# Power_Sensing.net
KiCad netlist of a schematic drawn in Altium Designer
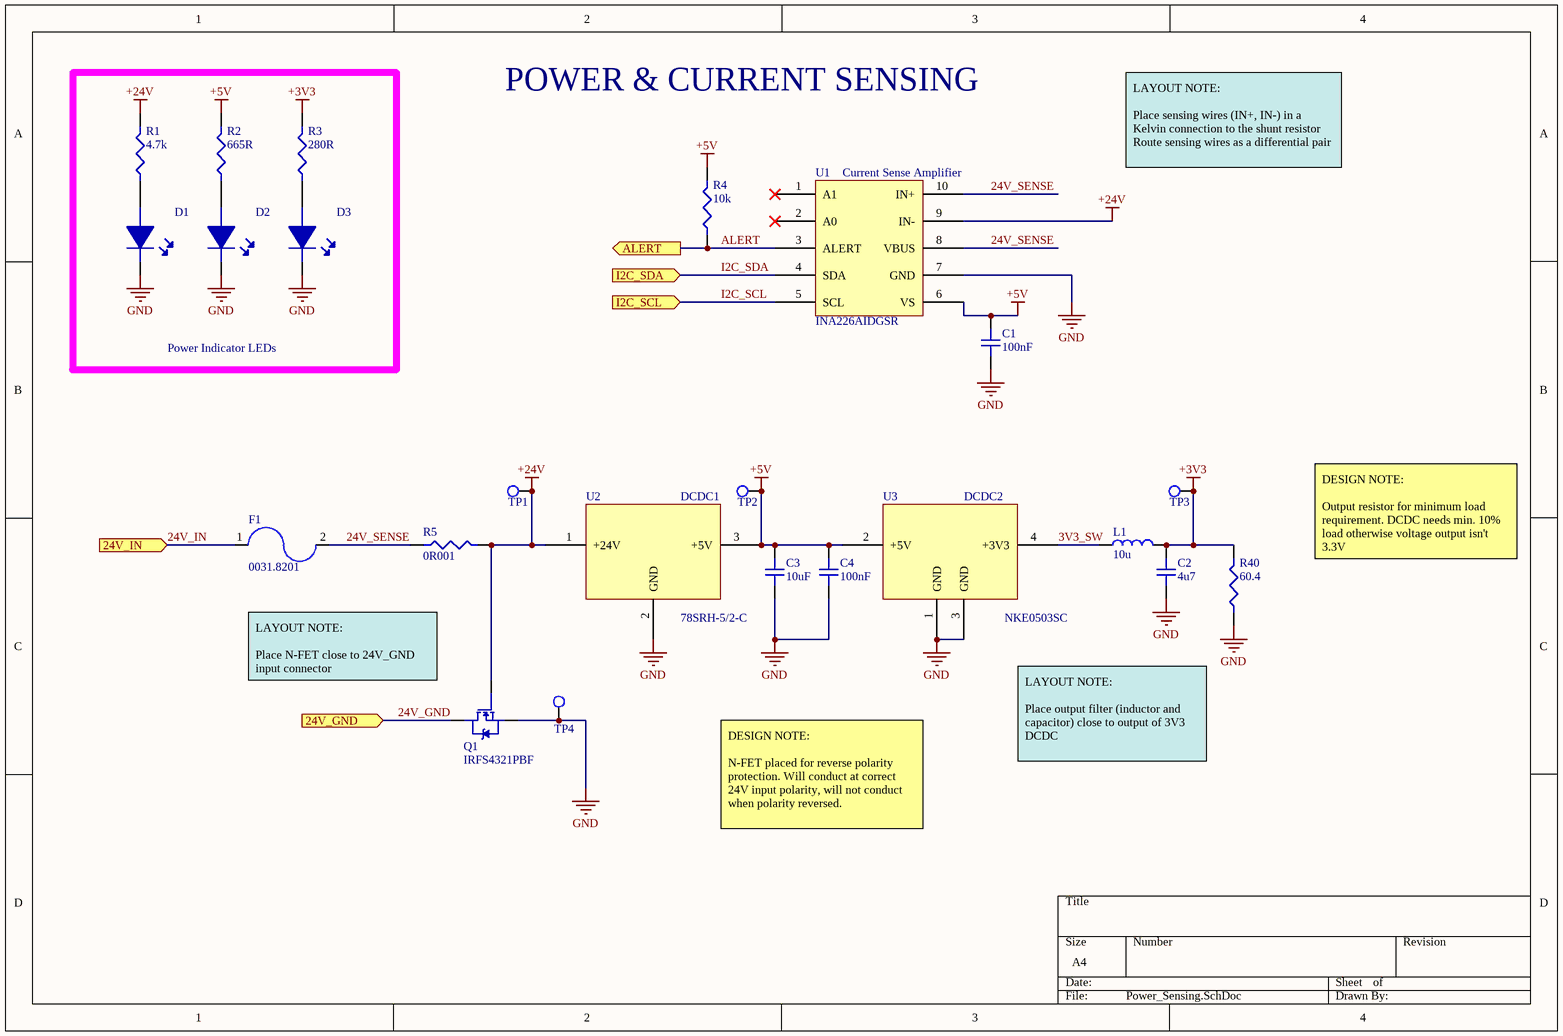
[diagram p0: Power_Sensing.SchDoc]

(export (version "E")
  (design (tool "Eeschema 10.0.6"))
  (components
    (comp (ref "C1")
      (value "100nF")
      (footprint "PHANTOM_FOOTPRINTS:C0805")
      (description "MLCC SMD CAP 100nF 10Volts U2J 5%")
      (fields
        (field (name "MANUFACTURER") "Murata")
        (field (name "MANUFACTURER PART NUMBER") "GRM21B7U1A104JA01L")
      )
      (libsource (lib "PHANTOM_LIBRARY") (part "GRM21B7U1A104JA01L"))
    )
    (comp (ref "C2")
      (value "4u7")
      (footprint "C0805")
      (fields
        (field (name "MANUFACTURER") "Murata")
        (field (name "MANUFACTURER PART NUMBER") "GRM219R61A475KE34D")
        (field (name "TOLERANCE") "10%")
      )
      (libsource (lib "PHANTOM_LIBRARY") (part "GRM219R61A475KE34D"))
    )
    (comp (ref "C3")
      (value "10uF")
      (footprint "TANT_10u")
      (fields
        (field (name "MANUFACTURER") "Kyocera AVX")
        (field (name "MANUFACTURER PART NUMBER") "F381A106MMA")
        (field (name "TOLERANCE") "20%")
      )
      (libsource (lib "PHANTOM_LIBRARY") (part "F381A106MMA"))
    )
    (comp (ref "C4")
      (value "100nF")
      (footprint "PHANTOM_FOOTPRINTS:C0805")
      (description "MLCC SMD CAP 100nF 10Volts U2J 5%")
      (fields
        (field (name "MANUFACTURER") "Murata")
        (field (name "MANUFACTURER PART NUMBER") "GRM21B7U1A104JA01L")
      )
      (libsource (lib "PHANTOM_LIBRARY") (part "GRM21B7U1A104JA01L"))
    )
    (comp (ref "D1")
      (value "LTST-C191KGKT")
      (footprint "LED_0603")
      (description "LED GREEN CLEAR 0603 SMD")
      (fields (field (name "MANUFACTURER") "Vishay Lite-On"))
      (libsource (lib "PHANTOM_LIBRARY") (part "LTST-C191KGKT"))
    )
    (comp (ref "D2")
      (value "LTST-C191KGKT")
      (footprint "LED_0603")
      (description "LED GREEN CLEAR 0603 SMD")
      (fields (field (name "MANUFACTURER") "Vishay Lite-On"))
      (libsource (lib "PHANTOM_LIBRARY") (part "LTST-C191KGKT"))
    )
    (comp (ref "D3")
      (value "LTST-C191KGKT")
      (footprint "LED_0603")
      (description "LED GREEN CLEAR 0603 SMD")
      (fields (field (name "MANUFACTURER") "Vishay Lite-On"))
      (libsource (lib "PHANTOM_LIBRARY") (part "LTST-C191KGKT"))
    )
    (comp (ref "F1")
      (value "0031.8201")
      (footprint "FUSE_HOLDER")
      (description "FUSE HOLDER, PCB, 20X5MM")
      (fields (field (name "MANUFACTURER") "Schurter") (field (name "VOLTAGE") "500V"))
      (libsource (lib "PHANTOM_LIBRARY") (part "0031.8201"))
    )
    (comp (ref "L1")
      (value "10u")
      (footprint "INDUCTOR")
      (description "Fixed Inductors 10uH 0.5A Mini SMT Power")
      (fields (field (name "MANUFACTURER") "Murata") (field (name "MANUFACTURER PART NUMBER") "82103C"))
      (libsource (lib "PHANTOM_LIBRARY") (part "82103C"))
    )
    (comp (ref "Q1")
      (value "IRFS4321PBF")
      (footprint "D2PAK_FETs")
      (description "MOSFET  N Channel, 83 A, 150 V, 0.012 ohm, 10 V, 5 V")
      (fields (field (name "MANUFACTURER") "Infineon"))
      (libsource (lib "PHANTOM_LIBRARY") (part "IRFS4321PBF"))
    )
    (comp (ref "R1")
      (value "4.7k")
      (footprint "R0805")
      (description "RES SMD 4.7K OHM 1% 1/8W 0805")
      (fields
        (field (name "MANUFACTURER") "Yageo")
        (field (name "MANUFACTURER PART NUMBER") "RC0805FR-074K7L")
      )
      (libsource (lib "PHANTOM_LIBRARY") (part "RC0805FR-074K7L"))
    )
    (comp (ref "R2")
      (value "665R")
      (footprint "R0805")
      (description "RES SMD 665 OHM 1% 1/8W 0805")
      (fields
        (field (name "MANUFACTURER") "Yageo")
        (field (name "MANUFACTURER PART NUMBER") "RC0805FR-07665RL")
      )
      (libsource (lib "PHANTOM_LIBRARY") (part "RC0805FR-07665RL"))
    )
    (comp (ref "R3")
      (value "280R")
      (footprint "R0805")
      (description "RES SMD 280 OHM 1% 1/8W 0805")
      (fields
        (field (name "MANUFACTURER") "Yageo")
        (field (name "MANUFACTURER PART NUMBER") "RC0805FR-07280RL")
      )
      (libsource (lib "PHANTOM_LIBRARY") (part "RC0805FR-07280RL"))
    )
    (comp (ref "R4")
      (value "10k")
      (footprint "R0805")
      (description "RES SMD 10K OHM 1% 1/8W 0805")
      (fields
        (field (name "MANUFACTURER") "Yageo Phycomp")
        (field (name "MANUFACTURER PART NUMBER") "RC0805FR-071KL")
      )
      (libsource (lib "PHANTOM_LIBRARY") (part "RC0805FR-071KL"))
    )
    (comp (ref "R5")
      (value "0R001")
      (footprint "R2512")
      (description "Res Thick Film 2512 0.001 Ohm 1% 1W 250ppm/C to 450ppm/C Molded SMD Embossed Carrier T/R")
      (fields
        (field (name "MANUFACTURER") "Panasonic ECG")
        (field (name "MANUFACTURER PART NUMBER") "ERJ-M1WTF1M0U")
      )
      (libsource (lib "PHANTOM_LIBRARY") (part "ERJ-M1WTF1M0U"))
    )
    (comp (ref "R40")
      (value "60.4")
      (footprint "R0805")
      (description "RES SMD 60.4 OHM 1% 1/8W 0805")
      (fields
        (field (name "MANUFACTURER") "Yageo")
        (field (name "MANUFACTURER PART NUMBER") "RC0805FR-0760R4L")
      )
      (libsource (lib "PHANTOM_LIBRARY") (part "RC0805FR-0760R4L"))
    )
    (comp (ref "TP1")
      (value "5015")
      (footprint "TP_HOOK")
      (description "TEST POINT, PCB, SMT")
      (fields (field (name "MANUFACTURER") "Keystone Electronics"))
      (libsource (lib "PHANTOM_LIBRARY") (part "5015"))
    )
    (comp (ref "TP2")
      (value "5015")
      (footprint "TP_HOOK")
      (description "TEST POINT, PCB, SMT")
      (fields (field (name "MANUFACTURER") "Keystone Electronics"))
      (libsource (lib "PHANTOM_LIBRARY") (part "5015"))
    )
    (comp (ref "TP3")
      (value "5015")
      (footprint "TP_HOOK")
      (description "TEST POINT, PCB, SMT")
      (fields (field (name "MANUFACTURER") "Keystone Electronics"))
      (libsource (lib "PHANTOM_LIBRARY") (part "5015"))
    )
    (comp (ref "TP4")
      (value "5015")
      (footprint "TP_HOOK")
      (description "TEST POINT, PCB, SMT")
      (fields (field (name "MANUFACTURER") "Keystone Electronics"))
      (libsource (lib "PHANTOM_LIBRARY") (part "5015"))
    )
    (comp (ref "U1")
      (value "INA226AIDGSR")
      (footprint "10-VSSOP_INA226")
      (description "IC MONITOR PWR/CURR BIDIR 10MSOP")
      (fields (field (name "MANUFACTURER") "Texas Instruments"))
      (libsource (lib "PHANTOM_LIBRARY") (part "INA226AIDGSR"))
    )
    (comp (ref "U2")
      (value "78SRH-5/2-C")
      (footprint "DCDC1")
      (description "MURATA POWER SOLUTIONS 	   	78SRH-5/2-C 	   	IC, SYNC SWITCHING REGULATOR, TO-220-3")
      (fields (field (name "MANUFACTURER") "Murata"))
      (libsource (lib "PHANTOM_LIBRARY") (part "78SRH-5/2-C"))
    )
    (comp (ref "U3")
      (value "NKE0503SC")
      (footprint "DCDC2")
      (description "DC/DC CONVERTER 3.3V 1W")
      (fields (field (name "MANUFACTURER") "Murata"))
      (libsource (lib "PHANTOM_LIBRARY") (part "NKE0503SC"))
    )
  )
  (nets
    (net (code "1") (name "+3V3") (class "Default")
      (node (ref "C2") (pin "2") (pinfunction "2_2") (pintype "passive"))
      (node (ref "L1") (pin "2") (pinfunction "2_2") (pintype "passive"))
      (node (ref "R3") (pin "2") (pinfunction "2_2") (pintype "passive"))
      (node (ref "R40") (pin "2") (pinfunction "2_2") (pintype "passive"))
      (node (ref "TP3") (pin "1") (pinfunction "1_1") (pintype "passive"))
    )
    (net (code "2") (name "+5V") (class "Default")
      (node (ref "C1") (pin "2") (pinfunction "2_2") (pintype "passive"))
      (node (ref "C3") (pin "2") (pinfunction "2_2") (pintype "passive"))
      (node (ref "C4") (pin "2") (pinfunction "2_2") (pintype "passive"))
      (node (ref "R2") (pin "2") (pinfunction "2_2") (pintype "passive"))
      (node (ref "R4") (pin "2") (pinfunction "2_2") (pintype "passive"))
      (node (ref "TP2") (pin "1") (pinfunction "1_1") (pintype "passive"))
      (node (ref "U1") (pin "6") (pinfunction "VS_6") (pintype "passive"))
      (node (ref "U2") (pin "3") (pinfunction "+5V_3") (pintype "passive"))
      (node (ref "U3") (pin "2") (pinfunction "+5V_2") (pintype "passive"))
    )
    (net (code "3") (name "+24V") (class "Default")
      (node (ref "Q1") (pin "1") (pinfunction "1_1") (pintype "passive"))
      (node (ref "R1") (pin "2") (pinfunction "2_2") (pintype "passive"))
      (node (ref "R5") (pin "2") (pinfunction "2_2") (pintype "passive"))
      (node (ref "TP1") (pin "1") (pinfunction "1_1") (pintype "passive"))
      (node (ref "U1") (pin "9") (pinfunction "IN-_9") (pintype "passive"))
      (node (ref "U2") (pin "1") (pinfunction "+24V_1") (pintype "passive"))
    )
    (net (code "4") (name "/3V3_SW") (class "Default")
      (node (ref "L1") (pin "1") (pinfunction "1_1") (pintype "passive"))
      (node (ref "U3") (pin "4") (pinfunction "+3V3_4") (pintype "passive"))
    )
    (net (code "5") (name "/24V_GND") (class "Default")
      (node (ref "Q1") (pin "4") (pinfunction "4_4") (pintype "passive"))
    )
    (net (code "6") (name "/24V_IN") (class "Default")
      (node (ref "F1") (pin "1") (pinfunction "1_1") (pintype "passive"))
    )
    (net (code "7") (name "/24V_SENSE") (class "Default")
      (node (ref "F1") (pin "2") (pinfunction "2_2") (pintype "passive"))
      (node (ref "R5") (pin "1") (pinfunction "1_1") (pintype "passive"))
      (node (ref "U1") (pin "10") (pinfunction "IN+_10") (pintype "passive"))
      (node (ref "U1") (pin "8") (pinfunction "VBUS_8") (pintype "passive"))
    )
    (net (code "8") (name "/ALERT") (class "Default")
      (node (ref "R4") (pin "1") (pinfunction "1_1") (pintype "passive"))
      (node (ref "U1") (pin "3") (pinfunction "ALERT_3") (pintype "passive"))
    )
    (net (code "9") (name "/I2C_SCL") (class "Default")
      (node (ref "U1") (pin "5") (pinfunction "SCL_5") (pintype "passive"))
    )
    (net (code "10") (name "/I2C_SDA") (class "Default")
      (node (ref "U1") (pin "4") (pinfunction "SDA_4") (pintype "passive"))
    )
    (net (code "11") (name "GND") (class "Default")
      (node (ref "C1") (pin "1") (pinfunction "1_1") (pintype "passive"))
      (node (ref "C2") (pin "1") (pinfunction "1_1") (pintype "passive"))
      (node (ref "C3") (pin "1") (pinfunction "1_1") (pintype "passive"))
      (node (ref "C4") (pin "1") (pinfunction "1_1") (pintype "passive"))
      (node (ref "D1") (pin "2") (pinfunction "2_2") (pintype "passive"))
      (node (ref "D2") (pin "2") (pinfunction "2_2") (pintype "passive"))
      (node (ref "D3") (pin "2") (pinfunction "2_2") (pintype "passive"))
      (node (ref "Q1") (pin "3") (pinfunction "3_3") (pintype "passive"))
      (node (ref "R40") (pin "1") (pinfunction "1_1") (pintype "passive"))
      (node (ref "TP4") (pin "1") (pinfunction "1_1") (pintype "passive"))
      (node (ref "U1") (pin "7") (pinfunction "GND_7") (pintype "passive"))
      (node (ref "U2") (pin "2") (pinfunction "GND_2") (pintype "passive"))
      (node (ref "U3") (pin "1") (pinfunction "GND_1") (pintype "passive"))
      (node (ref "U3") (pin "3") (pinfunction "GND_3") (pintype "passive"))
    )
    (net (code "12") (name "Net-(D1-Pad1)") (class "Default")
      (node (ref "D1") (pin "1") (pinfunction "1_1") (pintype "passive"))
      (node (ref "R1") (pin "1") (pinfunction "1_1") (pintype "passive"))
    )
    (net (code "13") (name "Net-(D2-Pad1)") (class "Default")
      (node (ref "D2") (pin "1") (pinfunction "1_1") (pintype "passive"))
      (node (ref "R2") (pin "1") (pinfunction "1_1") (pintype "passive"))
    )
    (net (code "14") (name "Net-(D3-Pad1)") (class "Default")
      (node (ref "D3") (pin "1") (pinfunction "1_1") (pintype "passive"))
      (node (ref "R3") (pin "1") (pinfunction "1_1") (pintype "passive"))
    )
    (net (code "15") (name "unconnected-(U1-A0-Pad2)") (class "Default")
      (node (ref "U1") (pin "2") (pinfunction "A0_2") (pintype "passive+no_connect"))
    )
    (net (code "16") (name "unconnected-(U1-A1-Pad1)") (class "Default")
      (node (ref "U1") (pin "1") (pinfunction "A1_1") (pintype "passive+no_connect"))
    )
  )
)
